# Regolatori_LM317.net
KiCad netlist of a schematic drawn in EAGLE
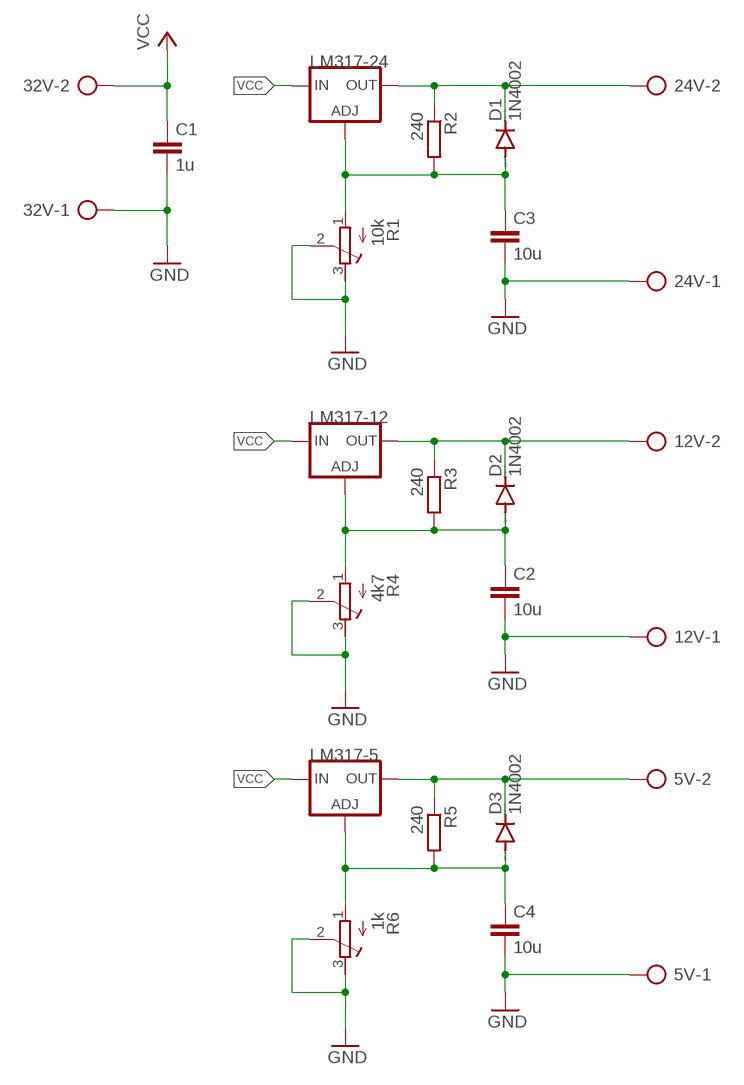
[diagram p0: schematic, sheet 1]

(export (version "E")
  (design (tool "Eeschema 10.0.6"))
  (components
    (comp (ref "5V")
      (value "SMKDSP_1,5/2")
      (footprint "eagle-import:SMKDSP_1,5_2")
      (fields (field (name "MF") "FARNELL") (field (name "MPN") "1733570"))
      (libsource (lib "eagle-import") (part "SMKDSP_1,5/2"))
    )
    (comp (ref "12V")
      (value "SMKDSP_1,5/2")
      (footprint "eagle-import:SMKDSP_1,5_2")
      (fields (field (name "MF") "FARNELL") (field (name "MPN") "1733570"))
      (libsource (lib "eagle-import") (part "SMKDSP_1,5/2"))
    )
    (comp (ref "24V")
      (value "SMKDSP_1,5/2")
      (footprint "eagle-import:SMKDSP_1,5_2")
      (fields (field (name "MF") "FARNELL") (field (name "MPN") "1733570"))
      (libsource (lib "eagle-import") (part "SMKDSP_1,5/2"))
    )
    (comp (ref "32V")
      (value "SMKDSP_1,5/2")
      (footprint "eagle-import:SMKDSP_1,5_2")
      (fields (field (name "MF") "FARNELL") (field (name "MPN") "1733570"))
      (libsource (lib "eagle-import") (part "SMKDSP_1,5/2"))
    )
    (comp (ref "C1")
      (value "1u")
      (footprint "eagle-import:C025-025X050")
      (libsource (lib "eagle-import") (part "C-EU025-025X050"))
    )
    (comp (ref "C2")
      (value "10u")
      (footprint "eagle-import:C025-025X050")
      (libsource (lib "eagle-import") (part "C-EU025-025X050"))
    )
    (comp (ref "C3")
      (value "10u")
      (footprint "eagle-import:C025-025X050")
      (libsource (lib "eagle-import") (part "C-EU025-025X050"))
    )
    (comp (ref "C4")
      (value "10u")
      (footprint "eagle-import:C025-025X050")
      (libsource (lib "eagle-import") (part "C-EU025-025X050"))
    )
    (comp (ref "D1")
      (value "1N4002")
      (footprint "eagle-import:DIOAD860W70L460D235B")
      (libsource (lib "eagle-import") (part "1N4004DO-41"))
    )
    (comp (ref "D2")
      (value "1N4002")
      (footprint "eagle-import:DIOAD860W70L460D235B")
      (libsource (lib "eagle-import") (part "1N4004DO-41"))
    )
    (comp (ref "D3")
      (value "1N4002")
      (footprint "eagle-import:DIOAD860W70L460D235B")
      (libsource (lib "eagle-import") (part "1N4004DO-41"))
    )
    (comp (ref "LM317-5")
      (value "LM317TS317TS_TO220")
      (footprint "eagle-import:TO220V")
      (libsource (lib "eagle-import") (part "LM317TS317TS_TO220"))
    )
    (comp (ref "LM317-12")
      (value "LM317TS317TS_TO220")
      (footprint "eagle-import:TO220V")
      (libsource (lib "eagle-import") (part "LM317TS317TS_TO220"))
    )
    (comp (ref "LM317-24")
      (value "LM317TS317TS_TO220")
      (footprint "eagle-import:TO220V")
      (libsource (lib "eagle-import") (part "LM317TS317TS_TO220"))
    )
    (comp (ref "R1")
      (value "10k")
      (footprint "eagle-import:RTRIM64W")
      (libsource (lib "eagle-import") (part "R-TRIMM64W"))
    )
    (comp (ref "R2")
      (value "240")
      (footprint "eagle-import:0204_7")
      (libsource (lib "eagle-import") (part "R-EU_0204/7"))
    )
    (comp (ref "R3")
      (value "240")
      (footprint "eagle-import:0204_7")
      (libsource (lib "eagle-import") (part "R-EU_0204/7"))
    )
    (comp (ref "R4")
      (value "4k7")
      (footprint "eagle-import:RTRIM64W")
      (libsource (lib "eagle-import") (part "R-TRIMM64W"))
    )
    (comp (ref "R5")
      (value "240")
      (footprint "eagle-import:0204_7")
      (libsource (lib "eagle-import") (part "R-EU_0204/7"))
    )
    (comp (ref "R6")
      (value "1k")
      (footprint "eagle-import:RTRIM64W")
      (libsource (lib "eagle-import") (part "R-TRIMM64W"))
    )
  )
  (nets
    (net (code "1") (name "GND") (class "Default")
      (node (ref "12V") (pin "1") (pinfunction "KL_1") (pintype "passive"))
      (node (ref "24V") (pin "1") (pinfunction "KL_1") (pintype "passive"))
      (node (ref "32V") (pin "1") (pinfunction "KL_1") (pintype "passive"))
      (node (ref "5V") (pin "1") (pinfunction "KL_1") (pintype "passive"))
      (node (ref "C1") (pin "2") (pinfunction "2_2") (pintype "passive"))
      (node (ref "C2") (pin "2") (pinfunction "2_2") (pintype "passive"))
      (node (ref "C3") (pin "2") (pinfunction "2_2") (pintype "passive"))
      (node (ref "C4") (pin "2") (pinfunction "2_2") (pintype "passive"))
      (node (ref "R1") (pin "2") (pinfunction "S_2") (pintype "passive"))
      (node (ref "R1") (pin "3") (pinfunction "E_3") (pintype "passive"))
      (node (ref "R4") (pin "2") (pinfunction "S_2") (pintype "passive"))
      (node (ref "R4") (pin "3") (pinfunction "E_3") (pintype "passive"))
      (node (ref "R6") (pin "2") (pinfunction "S_2") (pintype "passive"))
      (node (ref "R6") (pin "3") (pinfunction "E_3") (pintype "passive"))
    )
    (net (code "2") (name "Net-(5VB-KL)") (class "Default")
      (node (ref "5V") (pin "2") (pinfunction "KL_2") (pintype "passive"))
      (node (ref "D3") (pin "1") (pinfunction "C_1") (pintype "passive"))
      (node (ref "LM317-5") (pin "2") (pinfunction "OUT_2") (pintype "passive"))
      (node (ref "R5") (pin "1") (pinfunction "1_1") (pintype "passive"))
    )
    (net (code "3") (name "Net-(12VB-KL)") (class "Default")
      (node (ref "12V") (pin "2") (pinfunction "KL_2") (pintype "passive"))
      (node (ref "D2") (pin "1") (pinfunction "C_1") (pintype "passive"))
      (node (ref "LM317-12") (pin "2") (pinfunction "OUT_2") (pintype "passive"))
      (node (ref "R3") (pin "1") (pinfunction "1_1") (pintype "passive"))
    )
    (net (code "4") (name "Net-(24VB-KL)") (class "Default")
      (node (ref "24V") (pin "2") (pinfunction "KL_2") (pintype "passive"))
      (node (ref "D1") (pin "1") (pinfunction "C_1") (pintype "passive"))
      (node (ref "LM317-24") (pin "2") (pinfunction "OUT_2") (pintype "passive"))
      (node (ref "R2") (pin "1") (pinfunction "1_1") (pintype "passive"))
    )
    (net (code "5") (name "Net-(D1-A)") (class "Default")
      (node (ref "C3") (pin "1") (pinfunction "1_1") (pintype "passive"))
      (node (ref "D1") (pin "2") (pinfunction "A_2") (pintype "passive"))
      (node (ref "LM317-24") (pin "1") (pinfunction "ADJ_1") (pintype "input"))
      (node (ref "R1") (pin "1") (pinfunction "A_1") (pintype "passive"))
      (node (ref "R2") (pin "2") (pinfunction "2_2") (pintype "passive"))
    )
    (net (code "6") (name "Net-(D2-A)") (class "Default")
      (node (ref "C2") (pin "1") (pinfunction "1_1") (pintype "passive"))
      (node (ref "D2") (pin "2") (pinfunction "A_2") (pintype "passive"))
      (node (ref "LM317-12") (pin "1") (pinfunction "ADJ_1") (pintype "input"))
      (node (ref "R3") (pin "2") (pinfunction "2_2") (pintype "passive"))
      (node (ref "R4") (pin "1") (pinfunction "A_1") (pintype "passive"))
    )
    (net (code "7") (name "Net-(D3-A)") (class "Default")
      (node (ref "C4") (pin "1") (pinfunction "1_1") (pintype "passive"))
      (node (ref "D3") (pin "2") (pinfunction "A_2") (pintype "passive"))
      (node (ref "LM317-5") (pin "1") (pinfunction "ADJ_1") (pintype "input"))
      (node (ref "R5") (pin "2") (pinfunction "2_2") (pintype "passive"))
      (node (ref "R6") (pin "1") (pinfunction "A_1") (pintype "passive"))
    )
    (net (code "8") (name "VCC") (class "Default")
      (node (ref "32V") (pin "2") (pinfunction "KL_2") (pintype "passive"))
      (node (ref "C1") (pin "1") (pinfunction "1_1") (pintype "passive"))
      (node (ref "LM317-12") (pin "3") (pinfunction "IN_3") (pintype "input"))
      (node (ref "LM317-24") (pin "3") (pinfunction "IN_3") (pintype "input"))
      (node (ref "LM317-5") (pin "3") (pinfunction "IN_3") (pintype "input"))
    )
  )
)
